# EndEffector.net
KiCad netlist of a schematic drawn in EAGLE
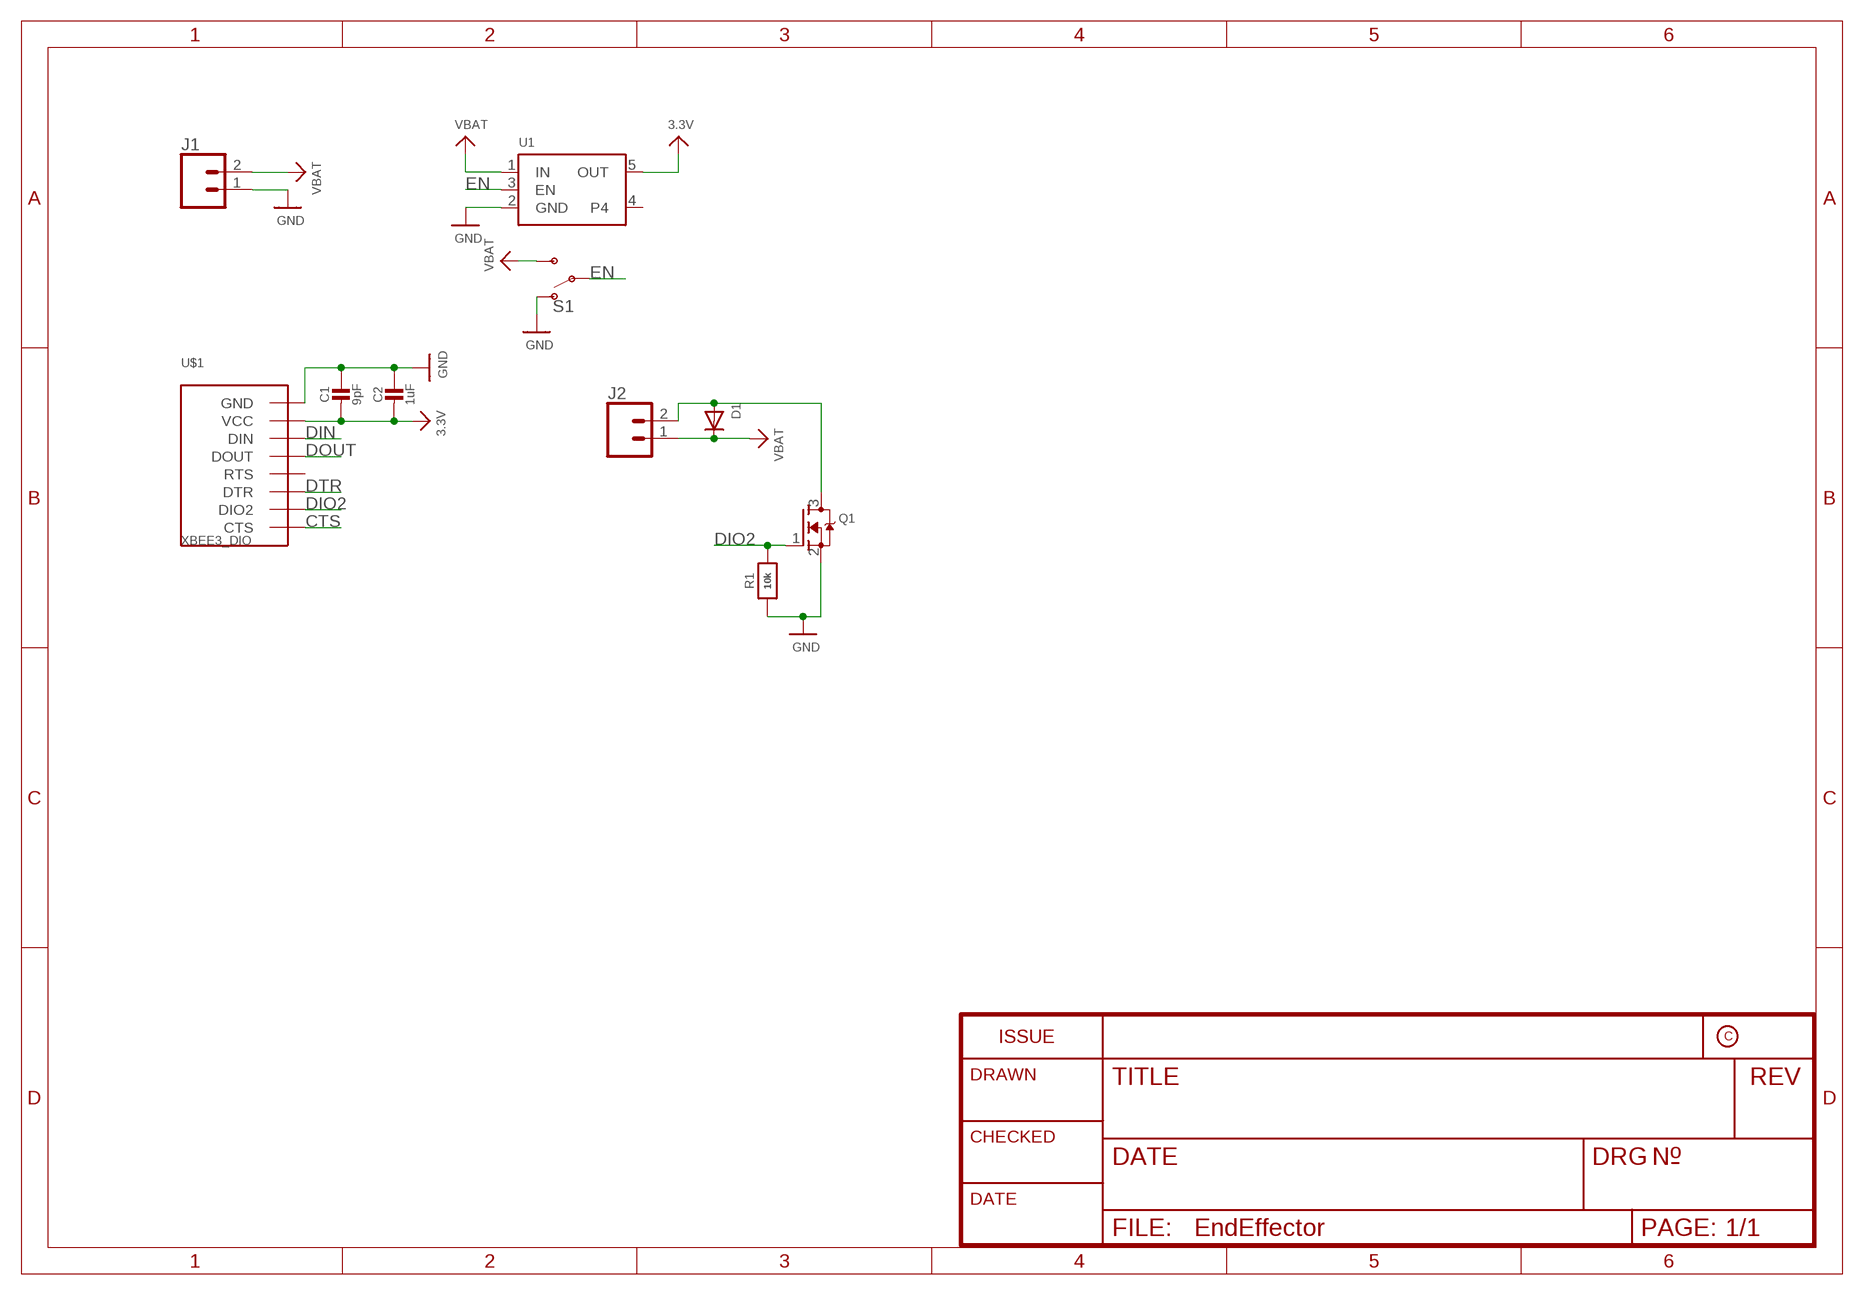
[diagram p0: schematic, sheet 1]

(export (version "E")
  (design (tool "Eeschema 10.0.6"))
  (components
    (comp (ref "C1")
      (value "9pF")
      (footprint "eagle-import:_0603")
      (libsource (lib "eagle-import") (part "CAP_CERAMIC_0603"))
    )
    (comp (ref "C2")
      (value "1uF")
      (footprint "eagle-import:_0603")
      (libsource (lib "eagle-import") (part "CAP_CERAMIC_0603"))
    )
    (comp (ref "D1")
      (value "DIODESOD-123")
      (footprint "eagle-import:SOD-123")
      (libsource (lib "eagle-import") (part "DIODESOD-123"))
    )
    (comp (ref "J1")
      (value "CONN_02")
      (footprint "eagle-import:1X02")
      (libsource (lib "eagle-import") (part "CONN_02"))
    )
    (comp (ref "J2")
      (value "CONN_02")
      (footprint "eagle-import:1X02")
      (libsource (lib "eagle-import") (part "CONN_02"))
    )
    (comp (ref "Q1")
      (value "MOSFET-NREFLOW")
      (footprint "eagle-import:SOT23")
      (libsource (lib "eagle-import") (part "MOSFET-NREFLOW"))
    )
    (comp (ref "R1")
      (value "10k")
      (footprint "eagle-import:_0603")
      (libsource (lib "eagle-import") (part "RESISTOR_0603"))
    )
    (comp (ref "S1")
      (value "SWITCH-SPDT-SMD-RIGHT-ANGLE")
      (footprint "eagle-import:SWITCH_SPST_SMD_A")
      (libsource (lib "eagle-import") (part "SWITCH-SPDT-SMD-RIGHT-ANGLE"))
    )
    (comp (ref "U$1")
      (value "XBEE3_DIO")
      (footprint "eagle-import:XBEE3_MICRO")
      (libsource (lib "eagle-import") (part "XBEE3_DIO"))
    )
    (comp (ref "U1")
      (value "VREG_SOT23-5")
      (footprint "eagle-import:SOT23-5")
      (libsource (lib "eagle-import") (part "VREG_SOT23-5"))
    )
  )
  (nets
    (net (code "1") (name "/CTS") (class "Default")
      (node (ref "U$1") (pin "CTS/DIO7") (pinfunction "CTS_CTS/DIO7") (pintype "bidirectional"))
    )
    (net (code "2") (name "/DIN") (class "Default")
      (node (ref "U$1") (pin "DIN/CONFIG/DIO14") (pinfunction "DIN_DIN/CONFIG/DIO14") (pintype "bidirectional"))
    )
    (net (code "3") (name "/DIO2") (class "Default")
      (node (ref "Q1") (pin "1") (pinfunction "G_1") (pintype "bidirectional"))
      (node (ref "R1") (pin "2") (pinfunction "2_2") (pintype "passive"))
      (node (ref "U$1") (pin "AD2/DIO2") (pinfunction "DIO2_AD2/DIO2") (pintype "bidirectional"))
    )
    (net (code "4") (name "/DOUT") (class "Default")
      (node (ref "U$1") (pin "DOUT/DIO13") (pinfunction "DOUT_DOUT/DIO13") (pintype "bidirectional"))
    )
    (net (code "5") (name "/DTR") (class "Default")
      (node (ref "U$1") (pin "DTR/SLEEP_RQ/DIO8") (pinfunction "DTR_DTR/SLEEP_RQ/DIO8") (pintype "bidirectional"))
    )
    (net (code "6") (name "/EN") (class "Default")
      (node (ref "S1") (pin "2") (pinfunction "P_2") (pintype "passive"))
      (node (ref "U1") (pin "3") (pinfunction "EN_3") (pintype "input"))
    )
    (net (code "7") (name "3.3V") (class "Default")
      (node (ref "C1") (pin "2") (pinfunction "2_2") (pintype "passive"))
      (node (ref "C2") (pin "2") (pinfunction "2_2") (pintype "passive"))
      (node (ref "U$1") (pin "VCC") (pinfunction "VCC_VCC") (pintype "bidirectional"))
      (node (ref "U1") (pin "5") (pinfunction "OUT_5") (pintype "power_in"))
    )
    (net (code "8") (name "GND") (class "Default")
      (node (ref "C1") (pin "1") (pinfunction "1_1") (pintype "passive"))
      (node (ref "C2") (pin "1") (pinfunction "1_1") (pintype "passive"))
      (node (ref "J1") (pin "1") (pinfunction "1_1") (pintype "passive"))
      (node (ref "Q1") (pin "2") (pinfunction "S_2") (pintype "bidirectional"))
      (node (ref "R1") (pin "1") (pinfunction "1_1") (pintype "passive"))
      (node (ref "S1") (pin "1") (pinfunction "O_1") (pintype "passive"))
      (node (ref "U$1") (pin "GND1") (pinfunction "GND_GND1") (pintype "bidirectional"))
      (node (ref "U$1") (pin "GND2") (pinfunction "GND_GND2") (pintype "bidirectional"))
      (node (ref "U$1") (pin "GND3") (pinfunction "GND_GND3") (pintype "bidirectional"))
      (node (ref "U$1") (pin "GND4") (pinfunction "GND_GND4") (pintype "bidirectional"))
      (node (ref "U$1") (pin "GND5") (pinfunction "GND_GND5") (pintype "bidirectional"))
      (node (ref "U$1") (pin "GND6") (pinfunction "GND_GND6") (pintype "bidirectional"))
      (node (ref "U1") (pin "2") (pinfunction "GND_2") (pintype "power_in"))
    )
    (net (code "9") (name "Net-(Q1-D)") (class "Default")
      (node (ref "D1") (pin "A") (pinfunction "A_A") (pintype "passive"))
      (node (ref "J2") (pin "2") (pinfunction "2_2") (pintype "passive"))
      (node (ref "Q1") (pin "3") (pinfunction "D_3") (pintype "bidirectional"))
    )
    (net (code "10") (name "VBAT") (class "Default")
      (node (ref "D1") (pin "C") (pinfunction "C_C") (pintype "passive"))
      (node (ref "J1") (pin "2") (pinfunction "2_2") (pintype "passive"))
      (node (ref "J2") (pin "1") (pinfunction "1_1") (pintype "passive"))
      (node (ref "S1") (pin "3") (pinfunction "S_3") (pintype "passive"))
      (node (ref "U1") (pin "1") (pinfunction "IN_1") (pintype "power_in"))
    )
    (net (code "11") (name "unconnected-(U$1-RTS-PadRTS{slash}DIO6)") (class "Default")
      (node (ref "U$1") (pin "RTS/DIO6") (pinfunction "RTS_RTS/DIO6") (pintype "bidirectional"))
    )
    (net (code "12") (name "unconnected-(U1-P4-Pad4)") (class "Default")
      (node (ref "U1") (pin "4") (pinfunction "P4_4") (pintype "bidirectional"))
    )
  )
)
